# Boost_5V.net
KiCad netlist of a schematic drawn in Altium Designer
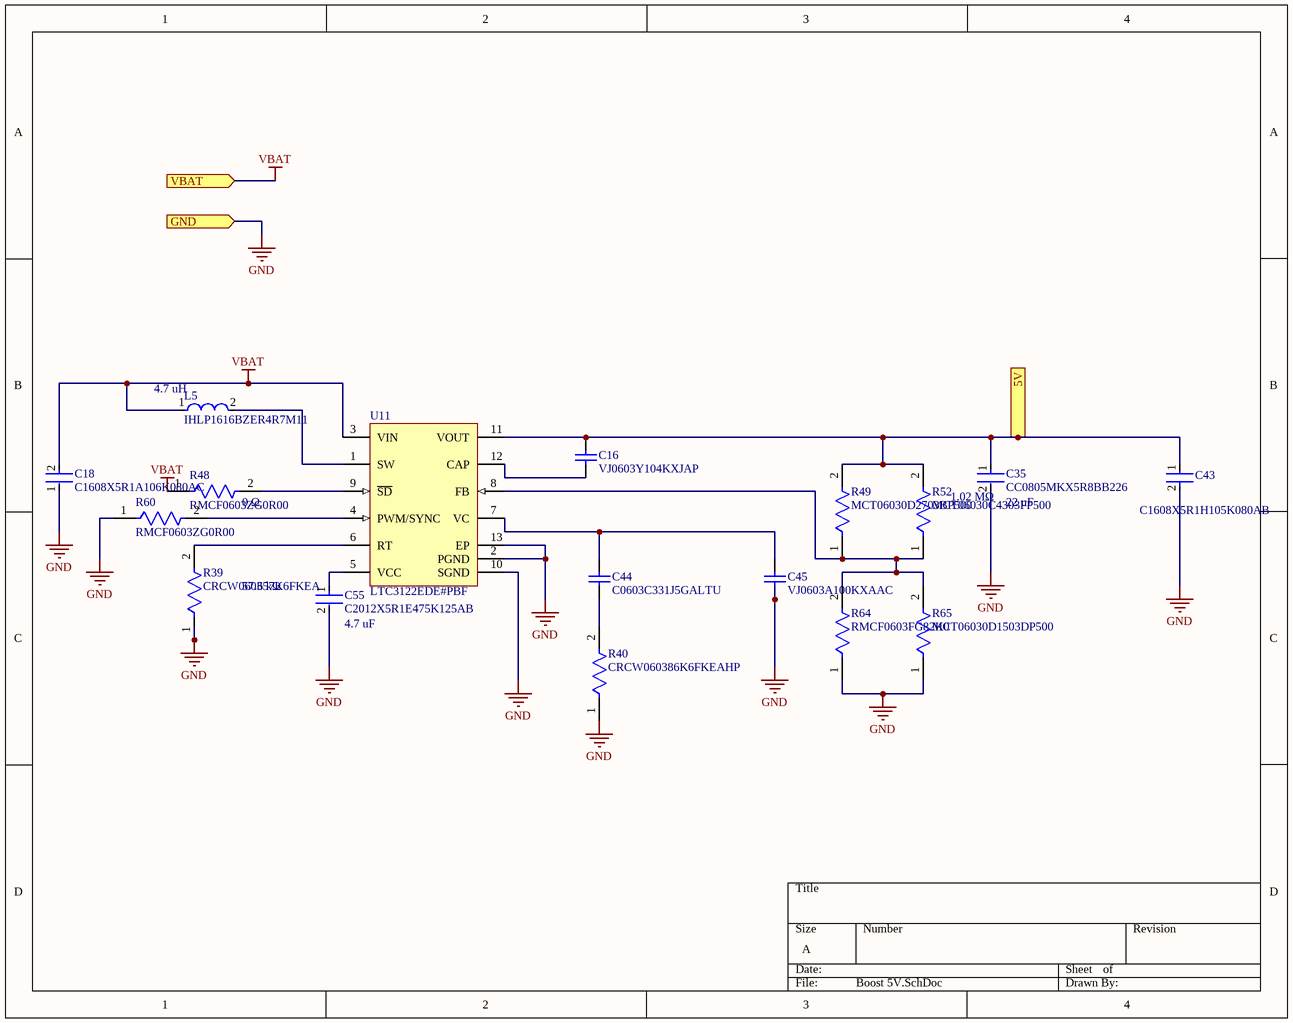
[diagram p0: Boost 5V.SchDoc]

(export (version "E")
  (design (tool "Eeschema 10.0.6"))
  (components
    (comp (ref "C16")
      (value "VJ0603Y104KXJAP")
      (footprint "CAPC1608X92X38NL15T08")
      (fields (field (name "MANUFACTURER") "Vitramon"))
      (libsource (lib "Altium Content Vault") (part "CAP"))
    )
    (comp (ref "C18")
      (value "C1608X5R1A106K080AC")
      (footprint "FP-C1608-080-0_1-MFG")
      (description "Multilayer Ceramic Capacitors 10μF ±10% 10V X5R SMD 0603")
      (fields (field (name "VOLTAGE") "10V") (field (name "TOLERANCE") "10%"))
      (libsource (lib "Altium Content Vault") (part "236180d848d6139a670b325ea6854c9"))
    )
    (comp (ref "C35")
      (value "CC0805MKX5R8BB226")
      (footprint "FP-CC0805-0_2-1_45-IPC_C")
      (description "CAP CER 22UF 25V X5R 0805")
      (fields (field (name "TOLERANCE") "20%"))
      (libsource (lib "Altium Content Vault") (part "11868f565c42a9108669ba33697ecf6"))
    )
    (comp (ref "C43")
      (value "C1608X5R1H105K080AB")
      (footprint "FP-C1608-080-0_1-IPC_B")
      (description "Multilayer Ceramic Capacitors 1μF ±10% 50V X5R SMD 0603")
      (fields (field (name "VOLTAGE") "50V") (field (name "TOLERANCE") "10%"))
      (libsource (lib "Altium Content Vault") (part "236180d848d6139a670b325ea6854c9"))
    )
    (comp (ref "C44")
      (value "C0603C331J5GALTU")
      (footprint "CAPC1608X87X35NL15T15")
      (fields (field (name "MANUFACTURER") "Kemet"))
      (libsource (lib "Altium Content Vault") (part "CAP"))
    )
    (comp (ref "C45")
      (value "VJ0603A100KXAAC")
      (footprint "CAPC1608X92X38ML12T08")
      (fields (field (name "MANUFACTURER") "Vitramon"))
      (libsource (lib "Altium Content Vault") (part "CAP"))
    )
    (comp (ref "C55")
      (value "C2012X5R1E475K125AB")
      (footprint "FP-C2012-125-0_2-MFG")
      (description "Multilayer Ceramic Capacitors 4.7μF ±10% 25V X5R SMD 0805")
      (fields (field (name "VOLTAGE") "25V") (field (name "TOLERANCE") "10%"))
      (libsource (lib "Altium Content Vault") (part "b4654b650e69147ec39a6b967a45e02"))
    )
    (comp (ref "L5")
      (value "IHLP1616BZER4R7M11")
      (footprint "FP-IHLP-1616BZ-FP_1_8545x-MFG")
      (description "Fixed Inductors Commercial Low DCR Series SMT 4.7uH 1.7A 105mΩ 20%")
      (fields (field (name "TOLERANCE") "20%"))
      (libsource (lib "Altium Content Vault") (part "725321dda6339637d4d059423bc1c3c"))
    )
    (comp (ref "R39")
      (value "CRCW060357K6FKEA")
      (footprint "FP-CRCW0603-e3-MFG")
      (description "RES Thick Film, 57.6kΩ, 1%, 0.1W, 100ppm/°C, 0603")
      (fields (field (name "TOLERANCE") "1%"))
      (libsource (lib "Altium Content Vault") (part "1029c3af85768c4190bb7ad29bc67b5"))
    )
    (comp (ref "R40")
      (value "CRCW060386K6FKEAHP")
      (footprint "FP-CRCW0603-HPe3-MFG")
      (description "RES Thick Film, 86.6kΩ, 1%, 0.33W, 100ppm/°C, 0603")
      (fields (field (name "TOLERANCE") "1%"))
      (libsource (lib "Altium Content Vault") (part "1029c3af85768c4190bb7ad29bc67b5"))
    )
    (comp (ref "R48")
      (value "RMCF0603ZG0R00")
      (footprint "FP-RMCF0603-IPC_B")
      (description "0Ω ±0 0.1W 0603 Thick Film Chip Resistor AEC-Q200 compliant")
      (libsource (lib "Altium Content Vault") (part "1029c3af85768c4190bb7ad29bc67b5"))
    )
    (comp (ref "R49")
      (value "MCT06030D2703BP500")
      (footprint "FP-MCT0603-IPC_A")
      (description "RES SMD 100 OHM 1% 1/8W 0603")
      (libsource (lib "Altium Content Vault") (part "1029c3af85768c4190bb7ad29bc67b5"))
    )
    (comp (ref "R52")
      (value "MCT06030C4303FP500")
      (footprint "FP-MCT0603-IPC_A")
      (description "RES SMD 100 OHM 1% 1/8W 0603")
      (fields (field (name "TOLERANCE") "1%"))
      (libsource (lib "Altium Content Vault") (part "1029c3af85768c4190bb7ad29bc67b5"))
    )
    (comp (ref "R60")
      (value "RMCF0603ZG0R00")
      (footprint "FP-RMCF0603-IPC_B")
      (description "0Ω ±0 0.1W 0603 Thick Film Chip Resistor AEC-Q200 compliant")
      (libsource (lib "Altium Content Vault") (part "1029c3af85768c4190bb7ad29bc67b5"))
    )
    (comp (ref "R64")
      (value "RMCF0603FG82K0")
      (footprint "FP-RMCF0603-IPC_C")
      (description "82kΩ ±1% 0.1W 0603 Thick Film Chip Resistor AEC-Q200 compliant")
      (fields (field (name "TOLERANCE") "1%"))
      (libsource (lib "Altium Content Vault") (part "1029c3af85768c4190bb7ad29bc67b5"))
    )
    (comp (ref "R65")
      (value "MCT06030D1503DP500")
      (footprint "FP-MCT0603-IPC_C")
      (description "RES SMD 100 OHM 1% 1/8W 0603")
      (fields (field (name "TOLERANCE") "0.5%"))
      (libsource (lib "Altium Content Vault") (part "1029c3af85768c4190bb7ad29bc67b5"))
    )
    (comp (ref "U11")
      (value "LTC3122EDE#PBF")
      (footprint "LT-DE-UE-12_V")
      (fields (field (name "MANUFACTURER") "Linear Technology"))
      (libsource (lib "Altium Content Vault") (part "LT-LTC3122-X-12"))
    )
  )
  (nets
    (net (code "1") (name "/5V") (class "Default")
      (node (ref "C16") (pin "2") (pinfunction "2_2") (pintype "passive"))
      (node (ref "C35") (pin "1") (pinfunction "1_1") (pintype "passive"))
      (node (ref "C43") (pin "1") (pinfunction "1_1") (pintype "passive"))
      (node (ref "R49") (pin "2") (pinfunction "2_2") (pintype "passive"))
      (node (ref "R52") (pin "2") (pinfunction "2_2") (pintype "passive"))
      (node (ref "U11") (pin "11") (pinfunction "VOUT_11") (pintype "power_in"))
    )
    (net (code "2") (name "GND") (class "Default")
      (node (ref "C18") (pin "1") (pinfunction "1_1") (pintype "passive"))
      (node (ref "C35") (pin "2") (pinfunction "2_2") (pintype "passive"))
      (node (ref "C43") (pin "2") (pinfunction "2_2") (pintype "passive"))
      (node (ref "C45") (pin "1") (pinfunction "1_1") (pintype "passive"))
      (node (ref "C55") (pin "2") (pinfunction "2_2") (pintype "passive"))
      (node (ref "R39") (pin "1") (pinfunction "1_1") (pintype "passive"))
      (node (ref "R40") (pin "1") (pinfunction "1_1") (pintype "passive"))
      (node (ref "R60") (pin "1") (pinfunction "1_1") (pintype "passive"))
      (node (ref "R64") (pin "1") (pinfunction "1_1") (pintype "passive"))
      (node (ref "R65") (pin "1") (pinfunction "1_1") (pintype "passive"))
      (node (ref "U11") (pin "10") (pinfunction "SGND_10") (pintype "power_in"))
      (node (ref "U11") (pin "13") (pinfunction "EP_13") (pintype "power_in"))
      (node (ref "U11") (pin "2") (pinfunction "PGND_2") (pintype "power_in"))
    )
    (net (code "3") (name "Net-(C44-Pad1)") (class "Default")
      (node (ref "C44") (pin "1") (pinfunction "1_1") (pintype "passive"))
      (node (ref "R40") (pin "2") (pinfunction "2_2") (pintype "passive"))
    )
    (net (code "4") (name "Net-(U11-CAP)") (class "Default")
      (node (ref "C16") (pin "1") (pinfunction "1_1") (pintype "passive"))
      (node (ref "U11") (pin "12") (pinfunction "CAP_12") (pintype "passive"))
    )
    (net (code "5") (name "Net-(U11-FB)") (class "Default")
      (node (ref "R49") (pin "1") (pinfunction "1_1") (pintype "passive"))
      (node (ref "R52") (pin "1") (pinfunction "1_1") (pintype "passive"))
      (node (ref "R64") (pin "2") (pinfunction "2_2") (pintype "passive"))
      (node (ref "R65") (pin "2") (pinfunction "2_2") (pintype "passive"))
      (node (ref "U11") (pin "8") (pinfunction "FB_8") (pintype "input"))
    )
    (net (code "6") (name "Net-(U11-PWM{slash}SYNC)") (class "Default")
      (node (ref "R60") (pin "2") (pinfunction "2_2") (pintype "passive"))
      (node (ref "U11") (pin "4") (pinfunction "PWM/SYNC_4") (pintype "input"))
    )
    (net (code "7") (name "Net-(U11-RT)") (class "Default")
      (node (ref "R39") (pin "2") (pinfunction "2_2") (pintype "passive"))
      (node (ref "U11") (pin "6") (pinfunction "RT_6") (pintype "passive"))
    )
    (net (code "8") (name "Net-(U11-SW)") (class "Default")
      (node (ref "L5") (pin "2") (pinfunction "2_2") (pintype "passive"))
      (node (ref "U11") (pin "1") (pinfunction "SW_1") (pintype "passive"))
    )
    (net (code "9") (name "Net-(U11-VC)") (class "Default")
      (node (ref "C44") (pin "2") (pinfunction "2_2") (pintype "passive"))
      (node (ref "C45") (pin "2") (pinfunction "2_2") (pintype "passive"))
      (node (ref "U11") (pin "7") (pinfunction "VC_7") (pintype "passive"))
    )
    (net (code "10") (name "Net-(U11-VCC)") (class "Default")
      (node (ref "C55") (pin "1") (pinfunction "1_1") (pintype "passive"))
      (node (ref "U11") (pin "5") (pinfunction "VCC_5") (pintype "power_in"))
    )
    (net (code "11") (name "Net-(U11-~{SD})") (class "Default")
      (node (ref "R48") (pin "2") (pinfunction "2_2") (pintype "passive"))
      (node (ref "U11") (pin "9") (pinfunction "~{SD}_9") (pintype "input"))
    )
    (net (code "12") (name "VBAT") (class "Default")
      (node (ref "C18") (pin "2") (pinfunction "2_2") (pintype "passive"))
      (node (ref "L5") (pin "1") (pinfunction "1_1") (pintype "passive"))
      (node (ref "R48") (pin "1") (pinfunction "1_1") (pintype "passive"))
      (node (ref "U11") (pin "3") (pinfunction "VIN_3") (pintype "power_in"))
    )
  )
)
